# Anchor_PCB_V1.net
KiCad netlist of a schematic drawn in EAGLE
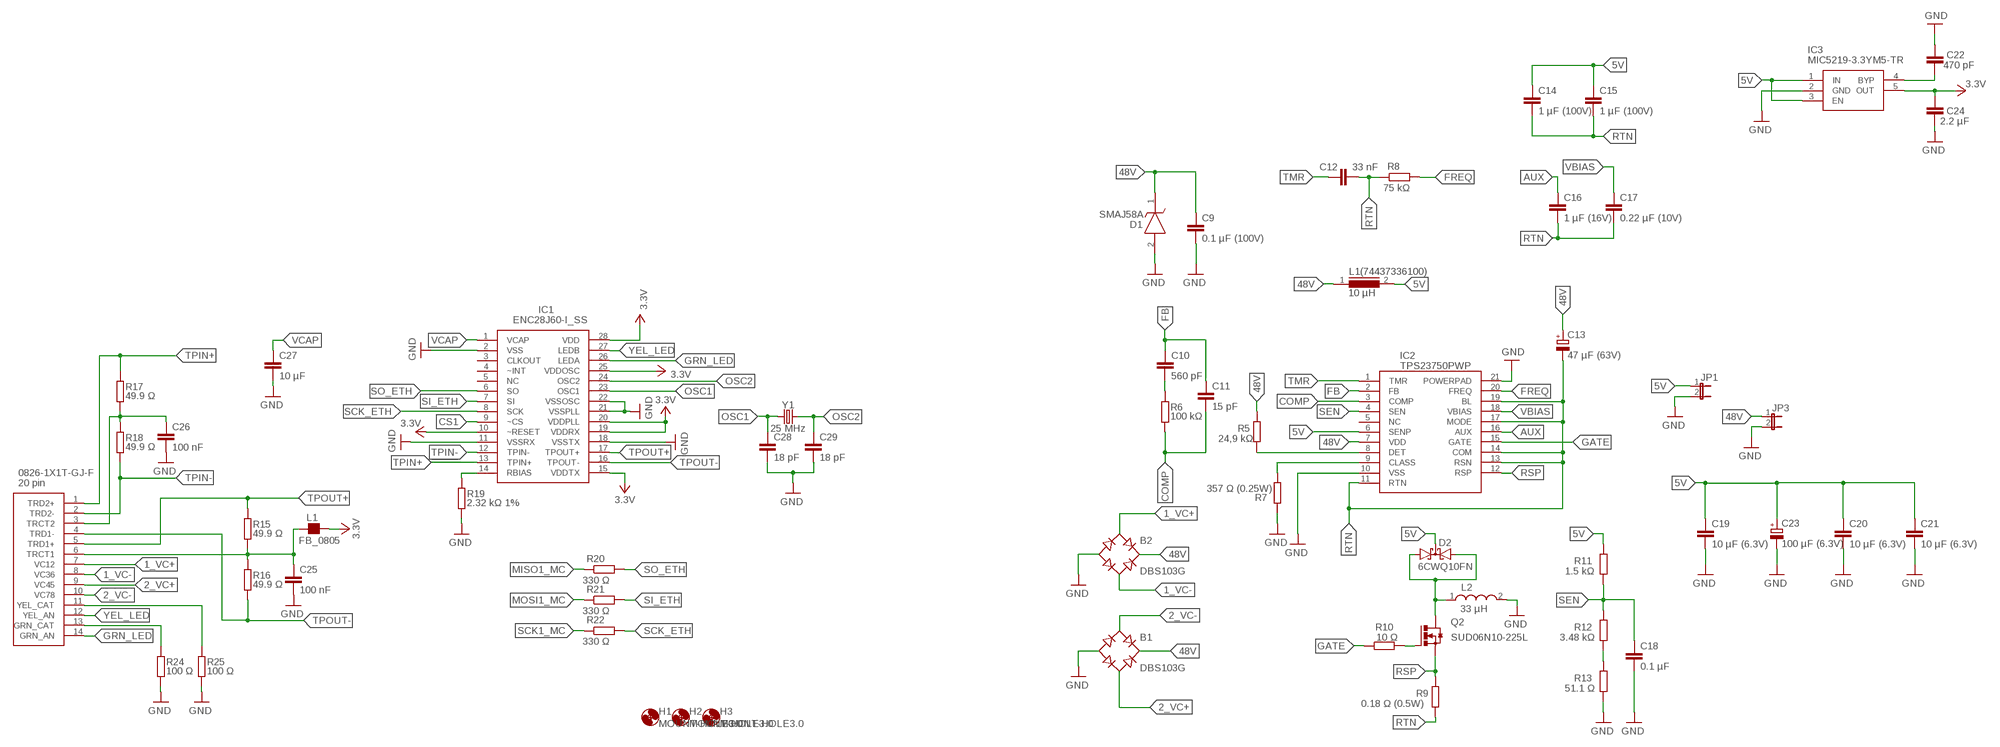
[diagram p0: schematic, sheet 1, part 1 of 2]
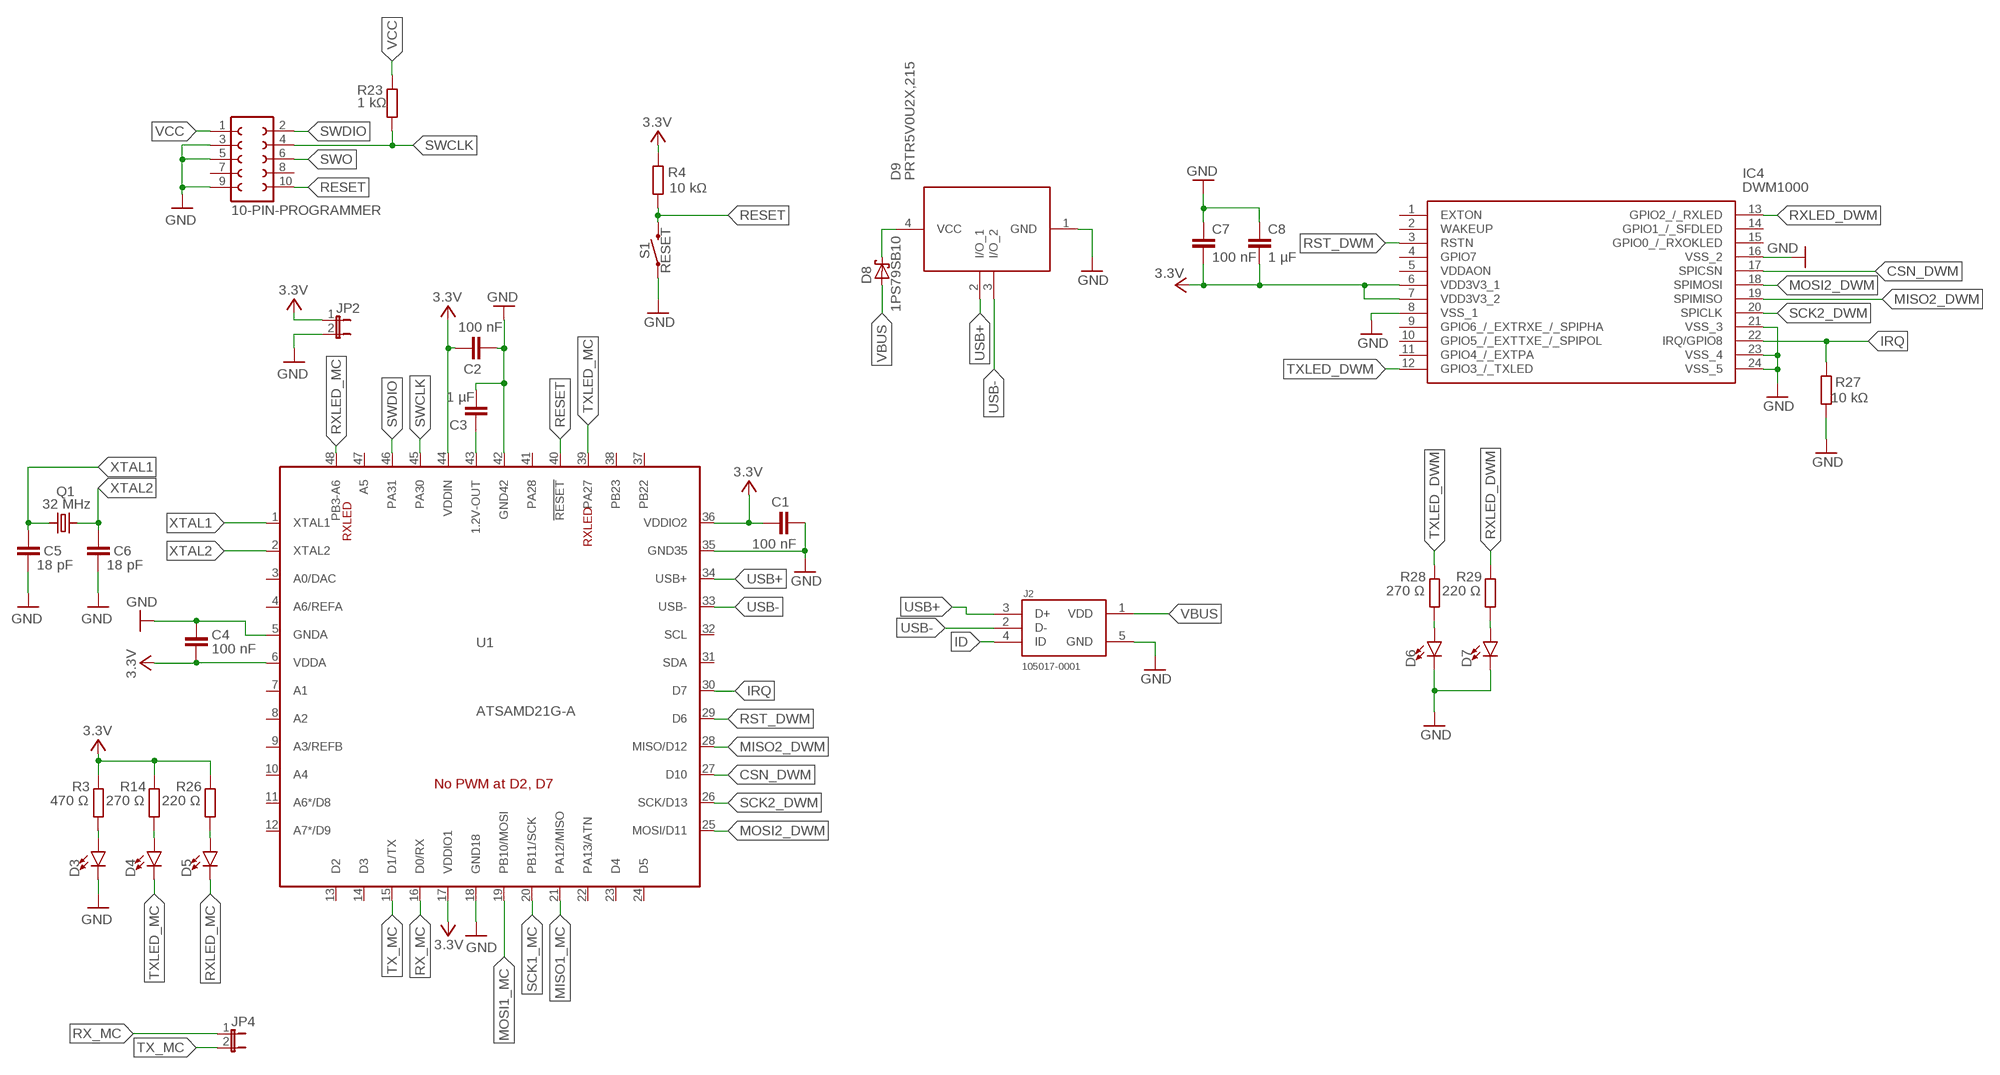
[diagram p1: schematic, sheet 1, part 2 of 2]

(export (version "E")
  (design (tool "Eeschema 10.0.6"))
  (components
    (comp (ref "10-PIN-PROGRAMMER")
      (value "FE05-2")
      (footprint "eagle-import:FE05-2")
      (libsource (lib "eagle-import") (part "FE05-2"))
    )
    (comp (ref "B1")
      (value "DBS103G")
      (footprint "eagle-import:DBS")
      (libsource (lib "eagle-import") (part "DB?GS103"))
    )
    (comp (ref "B2")
      (value "DBS103G")
      (footprint "eagle-import:DBS")
      (libsource (lib "eagle-import") (part "DB?GS103"))
    )
    (comp (ref "C1")
      (value "100 nF")
      (footprint "eagle-import:C0805")
      (libsource (lib "eagle-import") (part "C-EUC0805"))
    )
    (comp (ref "C2")
      (value "100 nF")
      (footprint "eagle-import:C0805")
      (libsource (lib "eagle-import") (part "C-EUC0805"))
    )
    (comp (ref "C3")
      (value "1 µF")
      (footprint "eagle-import:C0805")
      (libsource (lib "eagle-import") (part "C-EUC0805"))
    )
    (comp (ref "C4")
      (value "100 nF")
      (footprint "eagle-import:C0805")
      (libsource (lib "eagle-import") (part "C-EUC0805"))
    )
    (comp (ref "C5")
      (value "18 pF")
      (footprint "eagle-import:C0805")
      (libsource (lib "eagle-import") (part "C-EUC0805"))
    )
    (comp (ref "C6")
      (value "18 pF")
      (footprint "eagle-import:C0805")
      (libsource (lib "eagle-import") (part "C-EUC0805"))
    )
    (comp (ref "C7")
      (value "100 nF")
      (footprint "eagle-import:C0805")
      (libsource (lib "eagle-import") (part "C-EUC0805"))
    )
    (comp (ref "C8")
      (value "1 µF")
      (footprint "eagle-import:C0805")
      (libsource (lib "eagle-import") (part "C-EUC0805"))
    )
    (comp (ref "C9")
      (value "0.1 µF (100V)")
      (footprint "eagle-import:C0805")
      (libsource (lib "eagle-import") (part "C-EUC0805"))
    )
    (comp (ref "C10")
      (value "560 pF")
      (footprint "eagle-import:C0805")
      (libsource (lib "eagle-import") (part "C-EUC0805"))
    )
    (comp (ref "C11")
      (value "15 pF")
      (footprint "eagle-import:C0805")
      (libsource (lib "eagle-import") (part "C-EUC0805"))
    )
    (comp (ref "C12")
      (value "33 nF")
      (footprint "eagle-import:C0805")
      (libsource (lib "eagle-import") (part "C-EUC0805"))
    )
    (comp (ref "C13")
      (value "47 µF (63V)")
      (footprint "eagle-import:E3,5-8")
      (libsource (lib "eagle-import") (part "CPOL-EUE3.5-8"))
    )
    (comp (ref "C14")
      (value "1 µF (100V)")
      (footprint "eagle-import:C0805")
      (libsource (lib "eagle-import") (part "C-EUC0805"))
    )
    (comp (ref "C15")
      (value "1 µF (100V)")
      (footprint "eagle-import:C0805")
      (libsource (lib "eagle-import") (part "C-EUC0805"))
    )
    (comp (ref "C16")
      (value "1 µF (16V)")
      (footprint "eagle-import:C0805")
      (libsource (lib "eagle-import") (part "C-EUC0805"))
    )
    (comp (ref "C17")
      (value "0.22 µF (10V)")
      (footprint "eagle-import:C0805")
      (libsource (lib "eagle-import") (part "C-EUC0805"))
    )
    (comp (ref "C18")
      (value "0.1 µF")
      (footprint "eagle-import:C0805")
      (libsource (lib "eagle-import") (part "C-EUC0805"))
    )
    (comp (ref "C19")
      (value "10 µF (6.3V)")
      (footprint "eagle-import:C0805")
      (libsource (lib "eagle-import") (part "C-EUC0805"))
    )
    (comp (ref "C20")
      (value "10 µF (6.3V)")
      (footprint "eagle-import:C0805")
      (libsource (lib "eagle-import") (part "C-EUC0805"))
    )
    (comp (ref "C21")
      (value "10 µF (6.3V)")
      (footprint "eagle-import:C0805")
      (libsource (lib "eagle-import") (part "C-EUC0805"))
    )
    (comp (ref "C22")
      (value "470 pF")
      (footprint "eagle-import:C0805")
      (libsource (lib "eagle-import") (part "C-EUC0805"))
    )
    (comp (ref "C23")
      (value "100 µF (6.3V)")
      (footprint "eagle-import:UD-6,3X7,7_NICHICON")
      (libsource (lib "eagle-import") (part "CPOL-EUUD-6,3X7,7"))
    )
    (comp (ref "C24")
      (value "2.2 µF")
      (footprint "eagle-import:C0805")
      (libsource (lib "eagle-import") (part "C-EUC0805"))
    )
    (comp (ref "C25")
      (value "100 nF")
      (footprint "eagle-import:C0805")
      (libsource (lib "eagle-import") (part "C-EUC0805"))
    )
    (comp (ref "C26")
      (value "100 nF")
      (footprint "eagle-import:C0805")
      (libsource (lib "eagle-import") (part "C-EUC0805"))
    )
    (comp (ref "C27")
      (value "10 µF")
      (footprint "eagle-import:C0805")
      (libsource (lib "eagle-import") (part "C-EUC0805"))
    )
    (comp (ref "C28")
      (value "18 pF")
      (footprint "eagle-import:C0805")
      (libsource (lib "eagle-import") (part "C-EUC0805"))
    )
    (comp (ref "C29")
      (value "18 pF")
      (footprint "eagle-import:C0805")
      (libsource (lib "eagle-import") (part "C-EUC0805"))
    )
    (comp (ref "D1")
      (value "SMAJ58A")
      (footprint "eagle-import:DIOM5026X229N")
      (fields (field (name "MOUSER_PART_NUMBER") "576-SMAJ58A") (field (name "RS_PART_NUMBER") "7645562P"))
      (libsource (lib "eagle-import") (part "SMAJ58A"))
    )
    (comp (ref "D2")
      (value "6CWQ10FN")
      (footprint "eagle-import:DPAK")
      (libsource (lib "eagle-import") (part "BAS70-05DPAK"))
    )
    (comp (ref "D3")
      (value "POWER")
      (footprint "eagle-import:CHIP-LED0805")
      (libsource (lib "eagle-import") (part "LEDCHIP-LED0805"))
    )
    (comp (ref "D4")
      (value "TX")
      (footprint "eagle-import:CHIP-LED0805")
      (libsource (lib "eagle-import") (part "LEDCHIP-LED0805"))
    )
    (comp (ref "D5")
      (value "RX")
      (footprint "eagle-import:CHIP-LED0805")
      (libsource (lib "eagle-import") (part "LEDCHIP-LED0805"))
    )
    (comp (ref "D6")
      (value "TX")
      (footprint "eagle-import:CHIP-LED0805")
      (libsource (lib "eagle-import") (part "LEDCHIP-LED0805"))
    )
    (comp (ref "D7")
      (value "RX")
      (footprint "eagle-import:CHIP-LED0805")
      (libsource (lib "eagle-import") (part "LEDCHIP-LED0805"))
    )
    (comp (ref "D8")
      (value "1PS79SB10")
      (footprint "eagle-import:SOD523")
      (libsource (lib "eagle-import") (part "1PS79SB10"))
    )
    (comp (ref "D9")
      (value "PRTR5V0U2X,215")
      (footprint "eagle-import:SOT-143B")
      (fields
        (field (name "MOUSER_PART_NUMBER") "771-PRTR5V0U2X-T/R")
        (field (name "RS_PART_NUMBER") "7258720P")
      )
      (libsource (lib "eagle-import") (part "PRTR5V0U2X,215"))
    )
    (comp (ref "H1")
      (value "MOUNT-HOLE3.0")
      (footprint "eagle-import:3,0")
      (libsource (lib "eagle-import") (part "MOUNT-HOLE3.0"))
    )
    (comp (ref "H2")
      (value "MOUNT-HOLE3.0")
      (footprint "eagle-import:3,0")
      (libsource (lib "eagle-import") (part "MOUNT-HOLE3.0"))
    )
    (comp (ref "H3")
      (value "MOUNT-HOLE3.0")
      (footprint "eagle-import:3,0")
      (libsource (lib "eagle-import") (part "MOUNT-HOLE3.0"))
    )
    (comp (ref "IC1")
      (value "ENC28J60-I_SS")
      (footprint "eagle-import:SOP65P780X200-28N")
      (fields (field (name "ARROW_PART_NUMBER") "ENC28J60-I/SS") (field (name "RS_PART_NUMBER") "7707755P"))
      (libsource (lib "eagle-import") (part "ENC28J60-I_SS"))
    )
    (comp (ref "IC2")
      (value "TPS23750PWP")
      (footprint "eagle-import:SOP65P640X120-21N")
      (fields (field (name "MOUSER_PART_NUMBER") "595-TPS23750PWP") (field (name "RS_PART_NUMBER") "6200824"))
      (libsource (lib "eagle-import") (part "TPS23750PWP"))
    )
    (comp (ref "IC3")
      (value "MIC5219-3.3YM5-TR")
      (footprint "eagle-import:SOT95P280X130-5N")
      (fields
        (field (name "MOUSER_PART_NUMBER") "998-MIC5219-3.3YM5TR")
        (field (name "RS_PART_NUMBER") "9101685P")
      )
      (libsource (lib "eagle-import") (part "MIC5219-3.3YM5-TR"))
    )
    (comp (ref "IC4")
      (value "DWM1000")
      (footprint "eagle-import:DWM1000")
      (libsource (lib "eagle-import") (part "DWM1000"))
    )
    (comp (ref "J1")
      (value "0826-1X1T-GJ-F")
      (footprint "eagle-import:0826-1X1T-GJ-F")
      (fields
        (field (name "MOUSER_PART_NUMBER") "530-0826-1X1T-GJ-F")
        (field (name "RS_PART_NUMBER") "7418562")
      )
      (libsource (lib "eagle-import") (part "0826-1X1T-GJ-F"))
    )
    (comp (ref "J2")
      (value "105017-0001")
      (footprint "eagle-import:MOLEX_105017-0001")
      (fields (field (name "MF") "Molex"))
      (libsource (lib "eagle-import") (part "105017-0001"))
    )
    (comp (ref "JP1")
      (value "JP1E")
      (footprint "eagle-import:JP1")
      (libsource (lib "eagle-import") (part "JP1E"))
    )
    (comp (ref "JP2")
      (value "JP1E")
      (footprint "eagle-import:JP1")
      (libsource (lib "eagle-import") (part "JP1E"))
    )
    (comp (ref "JP3")
      (value "JP1E")
      (footprint "eagle-import:JP1")
      (libsource (lib "eagle-import") (part "JP1E"))
    )
    (comp (ref "JP4")
      (value "JP1E")
      (footprint "eagle-import:JP1")
      (libsource (lib "eagle-import") (part "JP1E"))
    )
    (comp (ref "L1")
      (value "FB_0805")
      (footprint "eagle-import:L0805")
      (libsource (lib "eagle-import") (part "FB_0805"))
    )
    (comp (ref "L1(74437336100)")
      (value "10 µH")
      (footprint "eagle-import:DR73")
      (libsource (lib "eagle-import") (part "DR73"))
    )
    (comp (ref "L2")
      (value "33 µH")
      (footprint "eagle-import:WE-PD_1260_1245_1280_1210")
      (libsource (lib "eagle-import") (part "WE-PD_1260/1245/1280/1210"))
    )
    (comp (ref "Q1")
      (value "32 MHz")
      (footprint "eagle-import:ABS07")
      (libsource (lib "eagle-import") (part "CRYSTAL.ABS07"))
    )
    (comp (ref "Q2")
      (value "SUD06N10-225L")
      (footprint "eagle-import:SOT223")
      (libsource (lib "eagle-import") (part "N-HEXFET_?-SOT323IRLL014N"))
    )
    (comp (ref "R3")
      (value "470 Ω")
      (footprint "eagle-import:R0805")
      (libsource (lib "eagle-import") (part "R-EU_R0805"))
    )
    (comp (ref "R4")
      (value "10 kΩ")
      (footprint "eagle-import:M0805")
      (libsource (lib "eagle-import") (part "R-EU_M0805"))
    )
    (comp (ref "R5")
      (value "24,9 kΩ")
      (footprint "eagle-import:R0805")
      (libsource (lib "eagle-import") (part "R-EU_R0805"))
    )
    (comp (ref "R6")
      (value "100 kΩ")
      (footprint "eagle-import:R0805")
      (libsource (lib "eagle-import") (part "R-EU_R0805"))
    )
    (comp (ref "R7")
      (value "357 Ω (0.25W)")
      (footprint "eagle-import:R0805")
      (libsource (lib "eagle-import") (part "R-EU_R0805"))
    )
    (comp (ref "R8")
      (value "75 kΩ")
      (footprint "eagle-import:R0805")
      (libsource (lib "eagle-import") (part "R-EU_R0805"))
    )
    (comp (ref "R9")
      (value "0.18 Ω (0.5W)")
      (footprint "eagle-import:R2010")
      (libsource (lib "eagle-import") (part "R-EU_R2010"))
    )
    (comp (ref "R10")
      (value "10 Ω")
      (footprint "eagle-import:R0805")
      (libsource (lib "eagle-import") (part "R-EU_R0805"))
    )
    (comp (ref "R11")
      (value "1.5 kΩ")
      (footprint "eagle-import:R0805")
      (libsource (lib "eagle-import") (part "R-EU_R0805"))
    )
    (comp (ref "R12")
      (value "3.48 kΩ")
      (footprint "eagle-import:R0805")
      (libsource (lib "eagle-import") (part "R-EU_R0805"))
    )
    (comp (ref "R13")
      (value "51.1 Ω")
      (footprint "eagle-import:R0805")
      (libsource (lib "eagle-import") (part "R-EU_R0805"))
    )
    (comp (ref "R14")
      (value "270 Ω")
      (footprint "eagle-import:R0805")
      (libsource (lib "eagle-import") (part "R-EU_R0805"))
    )
    (comp (ref "R15")
      (value "49.9 Ω")
      (footprint "eagle-import:R0805")
      (libsource (lib "eagle-import") (part "R-EU_R0805"))
    )
    (comp (ref "R16")
      (value "49.9 Ω")
      (footprint "eagle-import:R0805")
      (libsource (lib "eagle-import") (part "R-EU_R0805"))
    )
    (comp (ref "R17")
      (value "49.9 Ω")
      (footprint "eagle-import:R0805")
      (libsource (lib "eagle-import") (part "R-EU_R0805"))
    )
    (comp (ref "R18")
      (value "49.9 Ω")
      (footprint "eagle-import:R0805")
      (libsource (lib "eagle-import") (part "R-EU_R0805"))
    )
    (comp (ref "R19")
      (value "2.32 kΩ 1%")
      (footprint "eagle-import:R0805")
      (libsource (lib "eagle-import") (part "R-EU_R0805"))
    )
    (comp (ref "R20")
      (value "330 Ω")
      (footprint "eagle-import:R0805")
      (libsource (lib "eagle-import") (part "R-EU_R0805"))
    )
    (comp (ref "R21")
      (value "330 Ω")
      (footprint "eagle-import:R0805")
      (libsource (lib "eagle-import") (part "R-EU_R0805"))
    )
    (comp (ref "R22")
      (value "330 Ω")
      (footprint "eagle-import:R0805")
      (libsource (lib "eagle-import") (part "R-EU_R0805"))
    )
    (comp (ref "R23")
      (value "1 kΩ")
      (footprint "eagle-import:R0805")
      (libsource (lib "eagle-import") (part "R-EU_R0805"))
    )
    (comp (ref "R24")
      (value "100 Ω")
      (footprint "eagle-import:R0805")
      (libsource (lib "eagle-import") (part "R-EU_R0805"))
    )
    (comp (ref "R25")
      (value "100 Ω")
      (footprint "eagle-import:R0805")
      (libsource (lib "eagle-import") (part "R-EU_R0805"))
    )
    (comp (ref "R26")
      (value "220 Ω")
      (footprint "eagle-import:R0805")
      (libsource (lib "eagle-import") (part "R-EU_R0805"))
    )
    (comp (ref "R27")
      (value "10 kΩ")
      (footprint "eagle-import:M0805")
      (libsource (lib "eagle-import") (part "R-EU_M0805"))
    )
    (comp (ref "R28")
      (value "270 Ω")
      (footprint "eagle-import:R0805")
      (libsource (lib "eagle-import") (part "R-EU_R0805"))
    )
    (comp (ref "R29")
      (value "220 Ω")
      (footprint "eagle-import:R0805")
      (libsource (lib "eagle-import") (part "R-EU_R0805"))
    )
    (comp (ref "S1")
      (value "RESET")
      (footprint "eagle-import:TACTILE_SWITCH_SMD_4.5MM")
      (libsource (lib "eagle-import") (part "MOMENTARY-SWITCH-SPST-SMD-4.5MM"))
    )
    (comp (ref "U1")
      (value "ATSAMD21G-A")
      (footprint "eagle-import:TQFP-48")
      (libsource (lib "eagle-import") (part "ATSAMD21G-A"))
    )
    (comp (ref "Y1")
      (value "25 MHz")
      (footprint "eagle-import:HC49UP")
      (libsource (lib "eagle-import") (part "CRYSTALSMD-HC49UP"))
    )
  )
  (nets
    (net (code "1") (name "1_VC+") (class "Default")
      (node (ref "B2") (pin "AC1") (pinfunction "AC1_AC1") (pintype "passive"))
      (node (ref "J1") (pin "7") (pinfunction "VC12_7") (pintype "bidirectional"))
    )
    (net (code "2") (name "1_VC-") (class "Default")
      (node (ref "B2") (pin "AC2") (pinfunction "AC2_AC2") (pintype "passive"))
      (node (ref "J1") (pin "8") (pinfunction "VC36_8") (pintype "bidirectional"))
    )
    (net (code "3") (name "2_VC+") (class "Default")
      (node (ref "B1") (pin "AC2") (pinfunction "AC2_AC2") (pintype "passive"))
      (node (ref "J1") (pin "9") (pinfunction "VC45_9") (pintype "bidirectional"))
    )
    (net (code "4") (name "2_VC-") (class "Default")
      (node (ref "B1") (pin "AC1") (pinfunction "AC1_AC1") (pintype "passive"))
      (node (ref "J1") (pin "10") (pinfunction "VC78_10") (pintype "bidirectional"))
    )
    (net (code "5") (name "5V") (class "Default")
      (node (ref "C14") (pin "1") (pinfunction "1_1") (pintype "passive"))
      (node (ref "C15") (pin "1") (pinfunction "1_1") (pintype "passive"))
      (node (ref "C19") (pin "1") (pinfunction "1_1") (pintype "passive"))
      (node (ref "C20") (pin "1") (pinfunction "1_1") (pintype "passive"))
      (node (ref "C21") (pin "1") (pinfunction "1_1") (pintype "passive"))
      (node (ref "C23") (pin "+") (pinfunction "+_+") (pintype "passive"))
      (node (ref "D2") (pin "4") (pinfunction "C_4") (pintype "passive"))
      (node (ref "IC2") (pin "6") (pinfunction "SENP_6") (pintype "bidirectional"))
      (node (ref "IC3") (pin "1") (pinfunction "IN_1") (pintype "bidirectional"))
      (node (ref "IC3") (pin "3") (pinfunction "EN_3") (pintype "bidirectional"))
      (node (ref "JP1") (pin "1") (pinfunction "1_1") (pintype "passive"))
      (node (ref "L1(74437336100)") (pin "2") (pinfunction "2_2") (pintype "passive"))
      (node (ref "R11") (pin "2") (pinfunction "2_2") (pintype "passive"))
    )
    (net (code "6") (name "48V") (class "Default")
      (node (ref "B1") (pin "+") (pinfunction "+_+") (pintype "passive"))
      (node (ref "B2") (pin "+") (pinfunction "+_+") (pintype "passive"))
      (node (ref "C13") (pin "+") (pinfunction "+_+") (pintype "passive"))
      (node (ref "C9") (pin "1") (pinfunction "1_1") (pintype "passive"))
      (node (ref "D1") (pin "1") (pinfunction "K_1") (pintype "bidirectional"))
      (node (ref "IC2") (pin "7") (pinfunction "VDD_7") (pintype "bidirectional"))
      (node (ref "JP3") (pin "1") (pinfunction "1_1") (pintype "passive"))
      (node (ref "L1(74437336100)") (pin "1") (pinfunction "1_1") (pintype "passive"))
      (node (ref "R5") (pin "2") (pinfunction "2_2") (pintype "passive"))
    )
    (net (code "7") (name "AUX") (class "Default")
      (node (ref "C16") (pin "1") (pinfunction "1_1") (pintype "passive"))
      (node (ref "IC2") (pin "16") (pinfunction "AUX_16") (pintype "bidirectional"))
    )
    (net (code "8") (name "COMP") (class "Default")
      (node (ref "C11") (pin "2") (pinfunction "2_2") (pintype "passive"))
      (node (ref "IC2") (pin "3") (pinfunction "COMP_3") (pintype "bidirectional"))
      (node (ref "R6") (pin "2") (pinfunction "2_2") (pintype "passive"))
    )
    (net (code "9") (name "CS1") (class "Default")
      (node (ref "IC1") (pin "9") (pinfunction "~{CS}_9") (pintype "bidirectional"))
    )
    (net (code "10") (name "CSN_DWM") (class "Default")
      (node (ref "IC4") (pin "17") (pinfunction "SPICSN_17") (pintype "bidirectional"))
      (node (ref "U1") (pin "27") (pinfunction "D10_27") (pintype "bidirectional"))
    )
    (net (code "11") (name "FB") (class "Default")
      (node (ref "C10") (pin "1") (pinfunction "1_1") (pintype "passive"))
      (node (ref "C11") (pin "1") (pinfunction "1_1") (pintype "passive"))
      (node (ref "IC2") (pin "2") (pinfunction "FB_2") (pintype "bidirectional"))
    )
    (net (code "12") (name "FREQ") (class "Default")
      (node (ref "IC2") (pin "20") (pinfunction "FREQ_20") (pintype "bidirectional"))
      (node (ref "R8") (pin "2") (pinfunction "2_2") (pintype "passive"))
    )
    (net (code "13") (name "GATE") (class "Default")
      (node (ref "IC2") (pin "15") (pinfunction "GATE_15") (pintype "bidirectional"))
      (node (ref "R10") (pin "1") (pinfunction "1_1") (pintype "passive"))
    )
    (net (code "14") (name "GND") (class "Default")
      (node (ref "10-PIN-PROGRAMMER") (pin "3") (pinfunction "3_3") (pintype "passive"))
      (node (ref "10-PIN-PROGRAMMER") (pin "5") (pinfunction "5_5") (pintype "passive"))
      (node (ref "10-PIN-PROGRAMMER") (pin "9") (pinfunction "9_9") (pintype "passive"))
      (node (ref "B1") (pin "-") (pinfunction "-_-") (pintype "passive"))
      (node (ref "B2") (pin "-") (pinfunction "-_-") (pintype "passive"))
      (node (ref "C1") (pin "2") (pinfunction "2_2") (pintype "passive"))
      (node (ref "C18") (pin "2") (pinfunction "2_2") (pintype "passive"))
      (node (ref "C19") (pin "2") (pinfunction "2_2") (pintype "passive"))
      (node (ref "C2") (pin "2") (pinfunction "2_2") (pintype "passive"))
      (node (ref "C20") (pin "2") (pinfunction "2_2") (pintype "passive"))
      (node (ref "C21") (pin "2") (pinfunction "2_2") (pintype "passive"))
      (node (ref "C22") (pin "1") (pinfunction "1_1") (pintype "passive"))
      (node (ref "C23") (pin "-") (pinfunction "-_-") (pintype "passive"))
      (node (ref "C24") (pin "2") (pinfunction "2_2") (pintype "passive"))
      (node (ref "C25") (pin "2") (pinfunction "2_2") (pintype "passive"))
      (node (ref "C26") (pin "2") (pinfunction "2_2") (pintype "passive"))
      (node (ref "C27") (pin "2") (pinfunction "2_2") (pintype "passive"))
      (node (ref "C28") (pin "2") (pinfunction "2_2") (pintype "passive"))
      (node (ref "C29") (pin "2") (pinfunction "2_2") (pintype "passive"))
      (node (ref "C3") (pin "2") (pinfunction "2_2") (pintype "passive"))
      (node (ref "C4") (pin "2") (pinfunction "2_2") (pintype "passive"))
      (node (ref "C5") (pin "2") (pinfunction "2_2") (pintype "passive"))
      (node (ref "C6") (pin "2") (pinfunction "2_2") (pintype "passive"))
      (node (ref "C7") (pin "1") (pinfunction "1_1") (pintype "passive"))
      (node (ref "C8") (pin "1") (pinfunction "1_1") (pintype "passive"))
      (node (ref "C9") (pin "2") (pinfunction "2_2") (pintype "passive"))
      (node (ref "D1") (pin "2") (pinfunction "A_2") (pintype "bidirectional"))
      (node (ref "D3") (pin "C") (pinfunction "C_C") (pintype "passive"))
      (node (ref "D6") (pin "C") (pinfunction "C_C") (pintype "passive"))
      (node (ref "D7") (pin "C") (pinfunction "C_C") (pintype "passive"))
      (node (ref "D9") (pin "1") (pinfunction "GND_1") (pintype "power_in"))
      (node (ref "IC1") (pin "11") (pinfunction "VSSRX_11") (pintype "bidirectional"))
      (node (ref "IC1") (pin "18") (pinfunction "VSSTX_18") (pintype "bidirectional"))
      (node (ref "IC1") (pin "2") (pinfunction "VSS_2") (pintype "bidirectional"))
      (node (ref "IC1") (pin "21") (pinfunction "VSSPLL_21") (pintype "bidirectional"))
      (node (ref "IC1") (pin "22") (pinfunction "VSSOSC_22") (pintype "bidirectional"))
      (node (ref "IC2") (pin "10") (pinfunction "VSS_10") (pintype "bidirectional"))
      (node (ref "IC2") (pin "21") (pinfunction "POWERPAD_21") (pintype "bidirectional"))
      (node (ref "IC3") (pin "2") (pinfunction "GND_2") (pintype "bidirectional"))
      (node (ref "IC4") (pin "16") (pinfunction "VSS_2_16") (pintype "bidirectional"))
      (node (ref "IC4") (pin "21") (pinfunction "VSS_3_21") (pintype "bidirectional"))
      (node (ref "IC4") (pin "23") (pinfunction "VSS_4_23") (pintype "bidirectional"))
      (node (ref "IC4") (pin "24") (pinfunction "VSS_5_24") (pintype "bidirectional"))
      (node (ref "IC4") (pin "8") (pinfunction "VSS_1_8") (pintype "bidirectional"))
      (node (ref "J2") (pin "5") (pinfunction "GND_5") (pintype "power_in"))
      (node (ref "JP1") (pin "2") (pinfunction "2_2") (pintype "passive"))
      (node (ref "JP2") (pin "2") (pinfunction "2_2") (pintype "passive"))
      (node (ref "JP3") (pin "2") (pinfunction "2_2") (pintype "passive"))
      (node (ref "L2") (pin "2") (pinfunction "2_2") (pintype "passive"))
      (node (ref "R13") (pin "1") (pinfunction "1_1") (pintype "passive"))
      (node (ref "R19") (pin "2") (pinfunction "2_2") (pintype "passive"))
      (node (ref "R24") (pin "2") (pinfunction "2_2") (pintype "passive"))
      (node (ref "R25") (pin "2") (pinfunction "2_2") (pintype "passive"))
      (node (ref "R27") (pin "1") (pinfunction "1_1") (pintype "passive"))
      (node (ref "R7") (pin "1") (pinfunction "1_1") (pintype "passive"))
      (node (ref "S1") (pin "2") (pinfunction "1_2") (pintype "passive"))
      (node (ref "S1") (pin "3") (pinfunction "1_3") (pintype "passive"))
      (node (ref "U1") (pin "18") (pinfunction "GND18_18") (pintype "bidirectional"))
      (node (ref "U1") (pin "35") (pinfunction "GND35_35") (pintype "bidirectional"))
      (node (ref "U1") (pin "42") (pinfunction "GND42_42") (pintype "bidirectional"))
      (node (ref "U1") (pin "5") (pinfunction "GNDA_5") (pintype "bidirectional"))
    )
    (net (code "15") (name "GRN_LED") (class "Default")
      (node (ref "IC1") (pin "26") (pinfunction "LEDA_26") (pintype "bidirectional"))
      (node (ref "J1") (pin "14") (pinfunction "GRN_AN_14") (pintype "bidirectional"))
    )
    (net (code "16") (name "ID") (class "Default")
      (node (ref "J2") (pin "4") (pinfunction "ID_4") (pintype "passive"))
    )
    (net (code "17") (name "IRQ") (class "Default")
      (node (ref "IC4") (pin "22") (pinfunction "IRQ/GPIO8_22") (pintype "bidirectional"))
      (node (ref "R27") (pin "2") (pinfunction "2_2") (pintype "passive"))
      (node (ref "U1") (pin "30") (pinfunction "D7_30") (pintype "bidirectional"))
    )
    (net (code "18") (name "MISO1_MC") (class "Default")
      (node (ref "R20") (pin "1") (pinfunction "1_1") (pintype "passive"))
      (node (ref "U1") (pin "21") (pinfunction "PA12/MISO_21") (pintype "bidirectional"))
    )
    (net (code "19") (name "MISO2_DWM") (class "Default")
      (node (ref "IC4") (pin "19") (pinfunction "SPIMISO_19") (pintype "bidirectional"))
      (node (ref "U1") (pin "28") (pinfunction "MISO/D12_28") (pintype "bidirectional"))
    )
    (net (code "20") (name "MOSI1_MC") (class "Default")
      (node (ref "R21") (pin "1") (pinfunction "1_1") (pintype "passive"))
      (node (ref "U1") (pin "19") (pinfunction "PB10/MOSI_19") (pintype "bidirectional"))
    )
    (net (code "21") (name "MOSI2_DWM") (class "Default")
      (node (ref "IC4") (pin "18") (pinfunction "SPIMOSI_18") (pintype "bidirectional"))
      (node (ref "U1") (pin "25") (pinfunction "MOSI/D11_25") (pintype "bidirectional"))
    )
    (net (code "22") (name "Net-(C10-Pad2)") (class "Default")
      (node (ref "C10") (pin "2") (pinfunction "2_2") (pintype "passive"))
      (node (ref "R6") (pin "1") (pinfunction "1_1") (pintype "passive"))
    )
    (net (code "23") (name "Net-(D2-A1)") (class "Default")
      (node (ref "D2") (pin "1") (pinfunction "A1_1") (pintype "passive"))
      (node (ref "D2") (pin "3") (pinfunction "A2_3") (pintype "passive"))
      (node (ref "L2") (pin "1") (pinfunction "1_1") (pintype "passive"))
      (node (ref "Q2") (pin "4") (pinfunction "D_4") (pintype "passive"))
    )
    (net (code "24") (name "Net-(D3-PadA)") (class "Default")
      (node (ref "D3") (pin "A") (pinfunction "A_A") (pintype "passive"))
      (node (ref "R3") (pin "1") (pinfunction "1_1") (pintype "passive"))
    )
    (net (code "25") (name "Net-(D4-PadA)") (class "Default")
      (node (ref "D4") (pin "A") (pinfunction "A_A") (pintype "passive"))
      (node (ref "R14") (pin "1") (pinfunction "1_1") (pintype "passive"))
    )
    (net (code "26") (name "Net-(D5-PadA)") (class "Default")
      (node (ref "D5") (pin "A") (pinfunction "A_A") (pintype "passive"))
      (node (ref "R26") (pin "1") (pinfunction "1_1") (pintype "passive"))
    )
    (net (code "27") (name "Net-(D6-PadA)") (class "Default")
      (node (ref "D6") (pin "A") (pinfunction "A_A") (pintype "passive"))
      (node (ref "R28") (pin "1") (pinfunction "1_1") (pintype "passive"))
    )
    (net (code "28") (name "Net-(D7-PadA)") (class "Default")
      (node (ref "D7") (pin "A") (pinfunction "A_A") (pintype "passive"))
      (node (ref "R29") (pin "1") (pinfunction "1_1") (pintype "passive"))
    )
    (net (code "29") (name "Net-(D8-K)") (class "Default")
      (node (ref "D8") (pin "1") (pinfunction "K_1") (pintype "passive"))
      (node (ref "D9") (pin "4") (pinfunction "VCC_4") (pintype "power_in"))
    )
    (net (code "30") (name "Net-(IC1-RBIAS)") (class "Default")
      (node (ref "IC1") (pin "14") (pinfunction "RBIAS_14") (pintype "bidirectional"))
      (node (ref "R19") (pin "1") (pinfunction "1_1") (pintype "passive"))
    )
    (net (code "31") (name "Net-(IC2-CLASS)") (class "Default")
      (node (ref "IC2") (pin "9") (pinfunction "CLASS_9") (pintype "bidirectional"))
      (node (ref "R7") (pin "2") (pinfunction "2_2") (pintype "passive"))
    )
    (net (code "32") (name "Net-(IC2-DET)") (class "Default")
      (node (ref "IC2") (pin "8") (pinfunction "DET_8") (pintype "bidirectional"))
      (node (ref "R5") (pin "1") (pinfunction "1_1") (pintype "passive"))
    )
    (net (code "33") (name "Net-(IC3-BYP)") (class "Default")
      (node (ref "C22") (pin "2") (pinfunction "2_2") (pintype "passive"))
      (node (ref "IC3") (pin "4") (pinfunction "BYP_4") (pintype "bidirectional"))
    )
    (net (code "34") (name "Net-(J1-GRN_CAT)") (class "Default")
      (node (ref "J1") (pin "13") (pinfunction "GRN_CAT_13") (pintype "bidirectional"))
      (node (ref "R24") (pin "1") (pinfunction "1_1") (pintype "passive"))
    )
    (net (code "35") (name "Net-(J1-TRCT1)") (class "Default")
      (node (ref "C25") (pin "1") (pinfunction "1_1") (pintype "passive"))
      (node (ref "J1") (pin "6") (pinfunction "TRCT1_6") (pintype "bidirectional"))
      (node (ref "L1") (pin "1") (pinfunction "1_1") (pintype "passive"))
      (node (ref "R15") (pin "2") (pinfunction "2_2") (pintype "passive"))
      (node (ref "R16") (pin "1") (pinfunction "1_1") (pintype "passive"))
    )
    (net (code "36") (name "Net-(J1-TRCT2)") (class "Default")
      (node (ref "C26") (pin "1") (pinfunction "1_1") (pintype "passive"))
      (node (ref "J1") (pin "3") (pinfunction "TRCT2_3") (pintype "bidirectional"))
      (node (ref "R17") (pin "2") (pinfunction "2_2") (pintype "passive"))
      (node (ref "R18") (pin "1") (pinfunction "1_1") (pintype "passive"))
    )
    (net (code "37") (name "Net-(J1-YEL_CAT)") (class "Default")
      (node (ref "J1") (pin "11") (pinfunction "YEL_CAT_11") (pintype "bidirectional"))
      (node (ref "R25") (pin "1") (pinfunction "1_1") (pintype "passive"))
    )
    (net (code "38") (name "Net-(Q2-G)") (class "Default")
      (node (ref "Q2") (pin "1") (pinfunction "G_1") (pintype "passive"))
      (node (ref "R10") (pin "2") (pinfunction "2_2") (pintype "passive"))
    )
    (net (code "39") (name "Net-(R12-Pad1)") (class "Default")
      (node (ref "R12") (pin "1") (pinfunction "1_1") (pintype "passive"))
      (node (ref "R13") (pin "2") (pinfunction "2_2") (pintype "passive"))
    )
    (net (code "40") (name "Net-(U1-1.2V-OUT)") (class "Default")
      (node (ref "C3") (pin "1") (pinfunction "1_1") (pintype "passive"))
      (node (ref "U1") (pin "43") (pinfunction "1.2V-OUT_43") (pintype "bidirectional"))
    )
    (net (code "41") (name "OSC1") (class "Default")
      (node (ref "C28") (pin "1") (pinfunction "1_1") (pintype "passive"))
      (node (ref "IC1") (pin "23") (pinfunction "OSC1_23") (pintype "bidirectional"))
      (node (ref "Y1") (pin "1") (pinfunction "1_1") (pintype "passive"))
    )
    (net (code "42") (name "OSC2") (class "Default")
      (node (ref "C29") (pin "1") (pinfunction "1_1") (pintype "passive"))
      (node (ref "IC1") (pin "24") (pinfunction "OSC2_24") (pintype "bidirectional"))
      (node (ref "Y1") (pin "2") (pinfunction "2_2") (pintype "passive"))
    )
    (net (code "43") (name "RESET") (class "Default")
      (node (ref "10-PIN-PROGRAMMER") (pin "10") (pinfunction "10_10") (pintype "passive"))
      (node (ref "R4") (pin "1") (pinfunction "1_1") (pintype "passive"))
      (node (ref "S1") (pin "1") (pinfunction "2_1") (pintype "passive"))
      (node (ref "S1") (pin "4") (pinfunction "2_4") (pintype "passive"))
      (node (ref "U1") (pin "40") (pinfunction "~{RESET}_40") (pintype "bidirectional"))
    )
    (net (code "44") (name "RSP") (class "Default")
      (node (ref "IC2") (pin "12") (pinfunction "RSP_12") (pintype "bidirectional"))
      (node (ref "Q2") (pin "3") (pinfunction "S_3") (pintype "passive"))
      (node (ref "R9") (pin "2") (pinfunction "2_2") (pintype "passive"))
    )
    (net (code "45") (name "RST_DWM") (class "Default")
      (node (ref "IC4") (pin "3") (pinfunction "RSTN_3") (pintype "bidirectional"))
      (node (ref "U1") (pin "29") (pinfunction "D6_29") (pintype "bidirectional"))
    )
    (net (code "46") (name "RTN") (class "Default")
      (node (ref "C12") (pin "2") (pinfunction "2_2") (pintype "passive"))
      (node (ref "C13") (pin "-") (pinfunction "-_-") (pintype "passive"))
      (node (ref "C14") (pin "2") (pinfunction "2_2") (pintype "passive"))
      (node (ref "C15") (pin "2") (pinfunction "2_2") (pintype "passive"))
      (node (ref "C16") (pin "2") (pinfunction "2_2") (pintype "passive"))
      (node (ref "C17") (pin "2") (pinfunction "2_2") (pintype "passive"))
      (node (ref "IC2") (pin "11") (pinfunction "RTN_11") (pintype "bidirectional"))
      (node (ref "IC2") (pin "13") (pinfunction "RSN_13") (pintype "bidirectional"))
      (node (ref "IC2") (pin "14") (pinfunction "COM_14") (pintype "bidirectional"))
      (node (ref "IC2") (pin "17") (pinfunction "MODE_17") (pintype "bidirectional"))
      (node (ref "IC2") (pin "19") (pinfunction "BL_19") (pintype "bidirectional"))
      (node (ref "R8") (pin "1") (pinfunction "1_1") (pintype "passive"))
      (node (ref "R9") (pin "1") (pinfunction "1_1") (pintype "passive"))
    )
    (net (code "47") (name "RXLED_DWM") (class "Default")
      (node (ref "IC4") (pin "13") (pinfunction "GPIO2_/_RXLED_13") (pintype "bidirectional"))
      (node (ref "R29") (pin "2") (pinfunction "2_2") (pintype "passive"))
    )
    (net (code "48") (name "RXLED_MC") (class "Default")
      (node (ref "D5") (pin "C") (pinfunction "C_C") (pintype "passive"))
      (node (ref "U1") (pin "48") (pinfunction "PB3-A6_48") (pintype "bidirectional"))
    )
    (net (code "49") (name "RX_MC") (class "Default")
      (node (ref "JP4") (pin "1") (pinfunction "1_1") (pintype "passive"))
      (node (ref "U1") (pin "16") (pinfunction "D0/RX_16") (pintype "bidirectional"))
    )
    (net (code "50") (name "SCK1_MC") (class "Default")
      (node (ref "R22") (pin "1") (pinfunction "1_1") (pintype "passive"))
      (node (ref "U1") (pin "20") (pinfunction "PB11/SCK_20") (pintype "bidirectional"))
    )
    (net (code "51") (name "SCK2_DWM") (class "Default")
      (node (ref "IC4") (pin "20") (pinfunction "SPICLK_20") (pintype "bidirectional"))
      (node (ref "U1") (pin "26") (pinfunction "SCK/D13_26") (pintype "bidirectional"))
    )
    (net (code "52") (name "SCK_ETH") (class "Default")
      (node (ref "IC1") (pin "8") (pinfunction "SCK_8") (pintype "bidirectional"))
      (node (ref "R22") (pin "2") (pinfunction "2_2") (pintype "passive"))
    )
    (net (code "53") (name "SEN") (class "Default")
      (node (ref "C18") (pin "1") (pinfunction "1_1") (pintype "passive"))
      (node (ref "IC2") (pin "4") (pinfunction "SEN_4") (pintype "bidirectional"))
      (node (ref "R11") (pin "1") (pinfunction "1_1") (pintype "passive"))
      (node (ref "R12") (pin "2") (pinfunction "2_2") (pintype "passive"))
    )
    (net (code "54") (name "SI_ETH") (class "Default")
      (node (ref "IC1") (pin "7") (pinfunction "SI_7") (pintype "bidirectional"))
      (node (ref "R21") (pin "2") (pinfunction "2_2") (pintype "passive"))
    )
    (net (code "55") (name "SO_ETH") (class "Default")
      (node (ref "IC1") (pin "6") (pinfunction "SO_6") (pintype "bidirectional"))
      (node (ref "R20") (pin "2") (pinfunction "2_2") (pintype "passive"))
    )
    (net (code "56") (name "SWCLK") (class "Default")
      (node (ref "10-PIN-PROGRAMMER") (pin "4") (pinfunction "4_4") (pintype "passive"))
      (node (ref "R23") (pin "1") (pinfunction "1_1") (pintype "passive"))
      (node (ref "U1") (pin "45") (pinfunction "PA30_45") (pintype "bidirectional"))
    )
    (net (code "57") (name "SWDIO") (class "Default")
      (node (ref "10-PIN-PROGRAMMER") (pin "2") (pinfunction "2_2") (pintype "passive"))
      (node (ref "U1") (pin "46") (pinfunction "PA31_46") (pintype "bidirectional"))
    )
    (net (code "58") (name "SWO") (class "Default")
      (node (ref "10-PIN-PROGRAMMER") (pin "6") (pinfunction "6_6") (pintype "passive"))
    )
    (net (code "59") (name "TMR") (class "Default")
      (node (ref "C12") (pin "1") (pinfunction "1_1") (pintype "passive"))
      (node (ref "IC2") (pin "1") (pinfunction "TMR_1") (pintype "bidirectional"))
    )
    (net (code "60") (name "TPIN+") (class "Default")
      (node (ref "IC1") (pin "13") (pinfunction "TPIN+_13") (pintype "bidirectional"))
      (node (ref "J1") (pin "1") (pinfunction "TRD2+_1") (pintype "bidirectional"))
      (node (ref "R17") (pin "1") (pinfunction "1_1") (pintype "passive"))
    )
    (net (code "61") (name "TPIN-") (class "Default")
      (node (ref "IC1") (pin "12") (pinfunction "TPIN-_12") (pintype "bidirectional"))
      (node (ref "J1") (pin "2") (pinfunction "TRD2-_2") (pintype "bidirectional"))
      (node (ref "R18") (pin "2") (pinfunction "2_2") (pintype "passive"))
    )
    (net (code "62") (name "TPOUT+") (class "Default")
      (node (ref "IC1") (pin "17") (pinfunction "TPOUT+_17") (pintype "bidirectional"))
      (node (ref "J1") (pin "5") (pinfunction "TRD1+_5") (pintype "bidirectional"))
      (node (ref "R15") (pin "1") (pinfunction "1_1") (pintype "passive"))
    )
    (net (code "63") (name "TPOUT-") (class "Default")
      (node (ref "IC1") (pin "16") (pinfunction "TPOUT-_16") (pintype "bidirectional"))
      (node (ref "J1") (pin "4") (pinfunction "TRD1-_4") (pintype "bidirectional"))
      (node (ref "R16") (pin "2") (pinfunction "2_2") (pintype "passive"))
    )
    (net (code "64") (name "TXLED_DWM") (class "Default")
      (node (ref "IC4") (pin "12") (pinfunction "GPIO3_/_TXLED_12") (pintype "bidirectional"))
      (node (ref "R28") (pin "2") (pinfunction "2_2") (pintype "passive"))
    )
    (net (code "65") (name "TXLED_MC") (class "Default")
      (node (ref "D4") (pin "C") (pinfunction "C_C") (pintype "passive"))
      (node (ref "U1") (pin "39") (pinfunction "PA27_39") (pintype "bidirectional"))
    )
    (net (code "66") (name "TX_MC") (class "Default")
      (node (ref "JP4") (pin "2") (pinfunction "2_2") (pintype "passive"))
      (node (ref "U1") (pin "15") (pinfunction "D1/TX_15") (pintype "bidirectional"))
    )
    (net (code "67") (name "USB+") (class "Default")
      (node (ref "D9") (pin "2") (pinfunction "I/O_1_2") (pintype "bidirectional"))
      (node (ref "J2") (pin "3") (pinfunction "D+_3") (pintype "bidirectional"))
      (node (ref "U1") (pin "34") (pinfunction "USB+_34") (pintype "bidirectional"))
    )
    (net (code "68") (name "USB-") (class "Default")
      (node (ref "D9") (pin "3") (pinfunction "I/O_2_3") (pintype "bidirectional"))
      (node (ref "J2") (pin "2") (pinfunction "D-_2") (pintype "bidirectional"))
      (node (ref "U1") (pin "33") (pinfunction "USB-_33") (pintype "bidirectional"))
    )
    (net (code "69") (name "VBIAS") (class "Default")
      (node (ref "C17") (pin "1") (pinfunction "1_1") (pintype "passive"))
      (node (ref "IC2") (pin "18") (pinfunction "VBIAS_18") (pintype "bidirectional"))
    )
    (net (code "70") (name "VBUS") (class "Default")
      (node (ref "D8") (pin "2") (pinfunction "A_2") (pintype "passive"))
      (node (ref "J2") (pin "1") (pinfunction "VDD_1") (pintype "power_in"))
    )
    (net (code "71") (name "VCAP") (class "Default")
      (node (ref "C27") (pin "1") (pinfunction "1_1") (pintype "passive"))
      (node (ref "IC1") (pin "1") (pinfunction "VCAP_1") (pintype "bidirectional"))
    )
    (net (code "72") (name "VCC") (class "Default")
      (node (ref "10-PIN-PROGRAMMER") (pin "1") (pinfunction "1_1") (pintype "passive"))
      (node (ref "C1") (pin "1") (pinfunction "1_1") (pintype "passive"))
      (node (ref "C2") (pin "1") (pinfunction "1_1") (pintype "passive"))
      (node (ref "C24") (pin "1") (pinfunction "1_1") (pintype "passive"))
      (node (ref "C4") (pin "1") (pinfunction "1_1") (pintype "passive"))
      (node (ref "C7") (pin "2") (pinfunction "2_2") (pintype "passive"))
      (node (ref "C8") (pin "2") (pinfunction "2_2") (pintype "passive"))
      (node (ref "IC1") (pin "10") (pinfunction "~{RESET}_10") (pintype "bidirectional"))
      (node (ref "IC1") (pin "15") (pinfunction "VDDTX_15") (pintype "bidirectional"))
      (node (ref "IC1") (pin "19") (pinfunction "VDDRX_19") (pintype "bidirectional"))
      (node (ref "IC1") (pin "20") (pinfunction "VDDPLL_20") (pintype "bidirectional"))
      (node (ref "IC1") (pin "25") (pinfunction "VDDOSC_25") (pintype "bidirectional"))
      (node (ref "IC1") (pin "28") (pinfunction "VDD_28") (pintype "bidirectional"))
      (node (ref "IC3") (pin "5") (pinfunction "OUT_5") (pintype "bidirectional"))
      (node (ref "IC4") (pin "6") (pinfunction "VDD3V3_1_6") (pintype "bidirectional"))
      (node (ref "IC4") (pin "7") (pinfunction "VDD3V3_2_7") (pintype "bidirectional"))
      (node (ref "JP2") (pin "1") (pinfunction "1_1") (pintype "passive"))
      (node (ref "L1") (pin "2") (pinfunction "2_2") (pintype "passive"))
      (node (ref "R14") (pin "2") (pinfunction "2_2") (pintype "passive"))
      (node (ref "R23") (pin "2") (pinfunction "2_2") (pintype "passive"))
      (node (ref "R26") (pin "2") (pinfunction "2_2") (pintype "passive"))
      (node (ref "R3") (pin "2") (pinfunction "2_2") (pintype "passive"))
      (node (ref "R4") (pin "2") (pinfunction "2_2") (pintype "passive"))
      (node (ref "U1") (pin "17") (pinfunction "VDDIO1_17") (pintype "bidirectional"))
      (node (ref "U1") (pin "36") (pinfunction "VDDIO2_36") (pintype "bidirectional"))
      (node (ref "U1") (pin "44") (pinfunction "VDDIN_44") (pintype "bidirectional"))
      (node (ref "U1") (pin "6") (pinfunction "VDDA_6") (pintype "bidirectional"))
    )
    (net (code "73") (name "XTAL1") (class "Default")
      (node (ref "C5") (pin "1") (pinfunction "1_1") (pintype "passive"))
      (node (ref "Q1") (pin "2") (pinfunction "2_2") (pintype "passive"))
      (node (ref "U1") (pin "1") (pinfunction "XTAL1_1") (pintype "bidirectional"))
    )
    (net (code "74") (name "XTAL2") (class "Default")
      (node (ref "C6") (pin "1") (pinfunction "1_1") (pintype "passive"))
      (node (ref "Q1") (pin "1") (pinfunction "1_1") (pintype "passive"))
      (node (ref "U1") (pin "2") (pinfunction "XTAL2_2") (pintype "bidirectional"))
    )
    (net (code "75") (name "YEL_LED") (class "Default")
      (node (ref "IC1") (pin "27") (pinfunction "LEDB_27") (pintype "bidirectional"))
      (node (ref "J1") (pin "12") (pinfunction "YEL_AN_12") (pintype "bidirectional"))
    )
    (net (code "76") (name "unconnected-(10-PIN-PROGRAMMER-Pad7)") (class "Default")
      (node (ref "10-PIN-PROGRAMMER") (pin "7") (pinfunction "7_7") (pintype "passive"))
    )
    (net (code "77") (name "unconnected-(10-PIN-PROGRAMMER-Pad8)") (class "Default")
      (node (ref "10-PIN-PROGRAMMER") (pin "8") (pinfunction "8_8") (pintype "passive"))
    )
    (net (code "78") (name "unconnected-(IC1-CLKOUT-Pad3)") (class "Default")
      (node (ref "IC1") (pin "3") (pinfunction "CLKOUT_3") (pintype "bidirectional"))
    )
    (net (code "79") (name "unconnected-(IC1-NC-Pad5)") (class "Default")
      (node (ref "IC1") (pin "5") (pinfunction "NC_5") (pintype "no_connect"))
    )
    (net (code "80") (name "unconnected-(IC1-~{INT}-Pad4)") (class "Default")
      (node (ref "IC1") (pin "4") (pinfunction "~{INT}_4") (pintype "bidirectional"))
    )
    (net (code "81") (name "unconnected-(IC2-NC-Pad5)") (class "Default")
      (node (ref "IC2") (pin "5") (pinfunction "NC_5") (pintype "no_connect"))
    )
    (net (code "82") (name "unconnected-(IC4-EXTON-Pad1)") (class "Default")
      (node (ref "IC4") (pin "1") (pinfunction "EXTON_1") (pintype "bidirectional"))
    )
    (net (code "83") (name "unconnected-(IC4-GPIO0_{slash}_RXOKLED-Pad15)") (class "Default")
      (node (ref "IC4") (pin "15") (pinfunction "GPIO0_/_RXOKLED_15") (pintype "bidirectional"))
    )
    (net (code "84") (name "unconnected-(IC4-GPIO1_{slash}_SFDLED-Pad14)") (class "Default")
      (node (ref "IC4") (pin "14") (pinfunction "GPIO1_/_SFDLED_14") (pintype "bidirectional"))
    )
    (net (code "85") (name "unconnected-(IC4-GPIO4_{slash}_EXTPA-Pad11)") (class "Default")
      (node (ref "IC4") (pin "11") (pinfunction "GPIO4_/_EXTPA_11") (pintype "bidirectional"))
    )
    (net (code "86") (name "unconnected-(IC4-GPIO5_{slash}_EXTTXE_{slash}_SPIPOL-Pad10)") (class "Default")
      (node (ref "IC4") (pin "10") (pinfunction "GPIO5_/_EXTTXE_/_SPIPOL_10") (pintype "bidirectional"))
    )
    (net (code "87") (name "unconnected-(IC4-GPIO6_{slash}_EXTRXE_{slash}_SPIPHA-Pad9)") (class "Default")
      (node (ref "IC4") (pin "9") (pinfunction "GPIO6_/_EXTRXE_/_SPIPHA_9") (pintype "bidirectional"))
    )
    (net (code "88") (name "unconnected-(IC4-GPIO7-Pad4)") (class "Default")
      (node (ref "IC4") (pin "4") (pinfunction "GPIO7_4") (pintype "bidirectional"))
    )
    (net (code "89") (name "unconnected-(IC4-VDDAON-Pad5)") (class "Default")
      (node (ref "IC4") (pin "5") (pinfunction "VDDAON_5") (pintype "bidirectional"))
    )
    (net (code "90") (name "unconnected-(IC4-WAKEUP-Pad2)") (class "Default")
      (node (ref "IC4") (pin "2") (pinfunction "WAKEUP_2") (pintype "bidirectional"))
    )
    (net (code "91") (name "unconnected-(U1-A0{slash}DAC-Pad3)") (class "Default")
      (node (ref "U1") (pin "3") (pinfunction "A0/DAC_3") (pintype "bidirectional"))
    )
    (net (code "92") (name "unconnected-(U1-A1-Pad7)") (class "Default")
      (node (ref "U1") (pin "7") (pinfunction "A1_7") (pintype "bidirectional"))
    )
    (net (code "93") (name "unconnected-(U1-A2-Pad8)") (class "Default")
      (node (ref "U1") (pin "8") (pinfunction "A2_8") (pintype "bidirectional"))
    )
    (net (code "94") (name "unconnected-(U1-A3{slash}REFB-Pad9)") (class "Default")
      (node (ref "U1") (pin "9") (pinfunction "A3/REFB_9") (pintype "bidirectional"))
    )
    (net (code "95") (name "unconnected-(U1-A4-Pad10)") (class "Default")
      (node (ref "U1") (pin "10") (pinfunction "A4_10") (pintype "bidirectional"))
    )
    (net (code "96") (name "unconnected-(U1-A5-Pad47)") (class "Default")
      (node (ref "U1") (pin "47") (pinfunction "A5_47") (pintype "bidirectional"))
    )
    (net (code "97") (name "unconnected-(U1-A6*{slash}D8-Pad11)") (class "Default")
      (node (ref "U1") (pin "11") (pinfunction "A6*/D8_11") (pintype "bidirectional"))
    )
    (net (code "98") (name "unconnected-(U1-A6{slash}REFA-Pad4)") (class "Default")
      (node (ref "U1") (pin "4") (pinfunction "A6/REFA_4") (pintype "bidirectional"))
    )
    (net (code "99") (name "unconnected-(U1-A7*{slash}D9-Pad12)") (class "Default")
      (node (ref "U1") (pin "12") (pinfunction "A7*/D9_12") (pintype "bidirectional"))
    )
    (net (code "100") (name "unconnected-(U1-D2-Pad13)") (class "Default")
      (node (ref "U1") (pin "13") (pinfunction "D2_13") (pintype "bidirectional"))
    )
    (net (code "101") (name "unconnected-(U1-D3-Pad14)") (class "Default")
      (node (ref "U1") (pin "14") (pinfunction "D3_14") (pintype "bidirectional"))
    )
    (net (code "102") (name "unconnected-(U1-D4-Pad23)") (class "Default")
      (node (ref "U1") (pin "23") (pinfunction "D4_23") (pintype "bidirectional"))
    )
    (net (code "103") (name "unconnected-(U1-D5-Pad24)") (class "Default")
      (node (ref "U1") (pin "24") (pinfunction "D5_24") (pintype "bidirectional"))
    )
    (net (code "104") (name "unconnected-(U1-PA13{slash}ATN-Pad22)") (class "Default")
      (node (ref "U1") (pin "22") (pinfunction "PA13/ATN_22") (pintype "bidirectional"))
    )
    (net (code "105") (name "unconnected-(U1-PA28-Pad41)") (class "Default")
      (node (ref "U1") (pin "41") (pinfunction "PA28_41") (pintype "bidirectional"))
    )
    (net (code "106") (name "unconnected-(U1-PB22-Pad37)") (class "Default")
      (node (ref "U1") (pin "37") (pinfunction "PB22_37") (pintype "bidirectional"))
    )
    (net (code "107") (name "unconnected-(U1-PB23-Pad38)") (class "Default")
      (node (ref "U1") (pin "38") (pinfunction "PB23_38") (pintype "bidirectional"))
    )
    (net (code "108") (name "unconnected-(U1-SCL-Pad32)") (class "Default")
      (node (ref "U1") (pin "32") (pinfunction "SCL_32") (pintype "bidirectional"))
    )
    (net (code "109") (name "unconnected-(U1-SDA-Pad31)") (class "Default")
      (node (ref "U1") (pin "31") (pinfunction "SDA_31") (pintype "bidirectional"))
    )
  )
)
